# filtroFinal-TC.net
KiCad netlist of a schematic drawn in Altium Designer
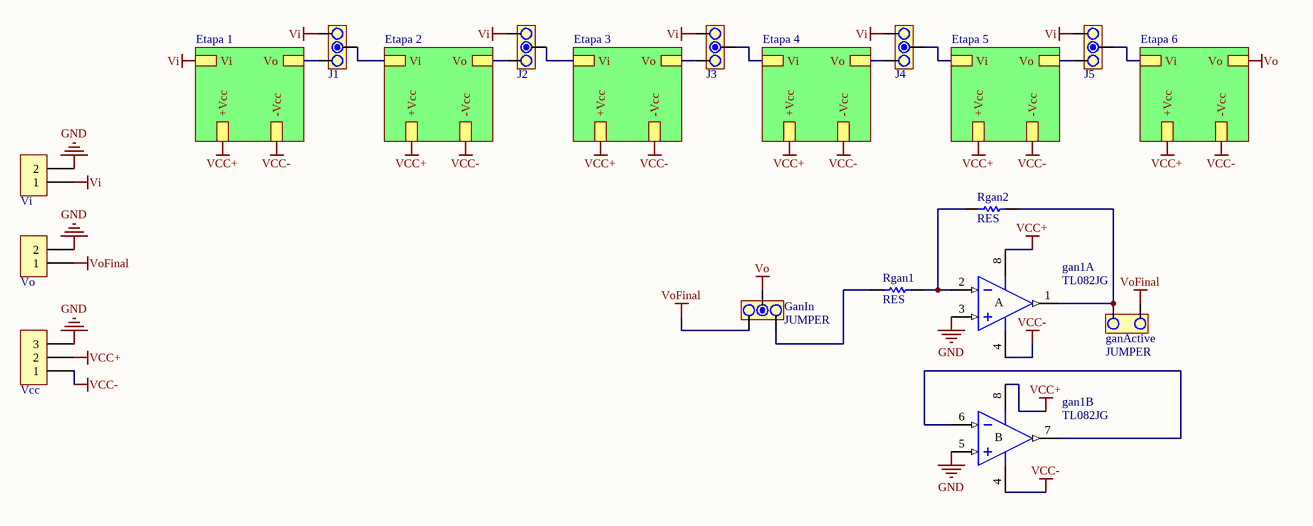
[diagram p0: filtroFinal-TC.SchDoc]

(export (version "E")
  (design (tool "Eeschema 10.0.6"))
  (components
    (comp (ref "gan1")
      (value "TL082JG")
      (footprint "JG008")
      (description "JFET-Input Operational Amplifier")
      (fields (field (name "PUBLISHER") "Altium Limited"))
      (libsource (lib "TI Operational Amplifier") (part "TL082JG"))
    )
    (comp (ref "ganActive")
      (value "JUMPER")
      (footprint "JUMPER2")
      (libsource (lib "LIBEBAL") (part "JUMPER"))
    )
    (comp (ref "GanIn") (value "JUMPER") (footprint "JUMPER3") (libsource (lib "") (part "JUMPER3_1")))
    (comp (ref "J1") (value "JUMPER") (footprint "JUMPER3") (libsource (lib "LIBEBAL") (part "JUMPER3")))
    (comp (ref "J2") (value "JUMPER") (footprint "JUMPER3") (libsource (lib "LIBEBAL") (part "JUMPER3")))
    (comp (ref "J3") (value "JUMPER") (footprint "JUMPER3") (libsource (lib "LIBEBAL") (part "JUMPER3")))
    (comp (ref "J4") (value "JUMPER") (footprint "JUMPER3") (libsource (lib "LIBEBAL") (part "JUMPER3")))
    (comp (ref "J5") (value "JUMPER") (footprint "JUMPER3") (libsource (lib "LIBEBAL") (part "JUMPER3")))
    (comp (ref "Rgan1") (value "RES") (footprint "RES300") (libsource (lib "LIBEBAL") (part "RES")))
    (comp (ref "Rgan2") (value "RES") (footprint "RES300") (libsource (lib "LIBEBAL") (part "RES")))
    (comp (ref "Vcc")
      (value "BORNERA 3")
      (footprint "BORNERA3")
      (libsource (lib "LIBEBAL") (part "BORNERA 3"))
    )
    (comp (ref "Vi")
      (value "BORNERA 2")
      (footprint "BORNERA2")
      (libsource (lib "LIBEBAL") (part "BORNERA 2"))
    )
    (comp (ref "Vo")
      (value "BORNERA 2")
      (footprint "BORNERA2")
      (libsource (lib "LIBEBAL") (part "BORNERA 2"))
    )
  )
  (nets
    (net (code "1") (name "/Vi") (class "Default")
      (node (ref "J2") (pin "2") (pinfunction "2_2") (pintype "passive"))
    )
    (net (code "2") (name "/Vi_1") (class "Default")
      (node (ref "J1") (pin "2") (pinfunction "2_2") (pintype "passive"))
    )
    (net (code "3") (name "/Vi_2") (class "Default")
      (node (ref "J3") (pin "2") (pinfunction "2_2") (pintype "passive"))
    )
    (net (code "4") (name "/Vi_3") (class "Default")
      (node (ref "J4") (pin "2") (pinfunction "2_2") (pintype "passive"))
    )
    (net (code "5") (name "/Vi_4") (class "Default")
      (node (ref "J5") (pin "2") (pinfunction "2_2") (pintype "passive"))
    )
    (net (code "6") (name "/Vo") (class "Default")
      (node (ref "J3") (pin "1") (pinfunction "1_1") (pintype "passive"))
    )
    (net (code "7") (name "/Vo_1") (class "Default")
      (node (ref "J1") (pin "1") (pinfunction "1_1") (pintype "passive"))
    )
    (net (code "8") (name "/Vo_2") (class "Default")
      (node (ref "J2") (pin "1") (pinfunction "1_1") (pintype "passive"))
    )
    (net (code "9") (name "/Vo_3") (class "Default")
      (node (ref "J4") (pin "1") (pinfunction "1_1") (pintype "passive"))
    )
    (net (code "10") (name "/Vo_4") (class "Default")
      (node (ref "J5") (pin "1") (pinfunction "1_1") (pintype "passive"))
    )
    (net (code "11") (name "GND") (class "Default")
      (node (ref "Vcc") (pin "3") (pinfunction "3_3") (pintype "passive"))
      (node (ref "Vi") (pin "2") (pinfunction "2_2") (pintype "passive"))
      (node (ref "Vo") (pin "2") (pinfunction "2_2") (pintype "passive"))
      (node (ref "gan1") (pin "3") (pinfunction "IN+_3") (pintype "input"))
      (node (ref "gan1") (pin "5") (pinfunction "IN+_5") (pintype "input"))
    )
    (net (code "12") (name "Net-(GanIn-Pad1)") (class "Default")
      (node (ref "GanIn") (pin "1") (pinfunction "1_1") (pintype "passive"))
      (node (ref "Rgan1") (pin "1") (pinfunction "1_1") (pintype "passive"))
    )
    (net (code "13") (name "Net-(gan1A-IN-)") (class "Default")
      (node (ref "Rgan1") (pin "2") (pinfunction "2_2") (pintype "passive"))
      (node (ref "Rgan2") (pin "1") (pinfunction "1_1") (pintype "passive"))
      (node (ref "gan1") (pin "2") (pinfunction "IN-_2") (pintype "input"))
    )
    (net (code "14") (name "Net-(gan1A-OUT)") (class "Default")
      (node (ref "Rgan2") (pin "2") (pinfunction "2_2") (pintype "passive"))
      (node (ref "gan1") (pin "1") (pinfunction "OUT_1") (pintype "output"))
      (node (ref "ganActive") (pin "1") (pinfunction "1_1") (pintype "passive"))
    )
    (net (code "15") (name "Net-(gan1B-IN-)") (class "Default")
      (node (ref "gan1") (pin "6") (pinfunction "IN-_6") (pintype "input"))
      (node (ref "gan1") (pin "7") (pinfunction "OUT_7") (pintype "output"))
    )
    (net (code "16") (name "VCC+") (class "Default")
      (node (ref "Vcc") (pin "2") (pinfunction "2_2") (pintype "passive"))
      (node (ref "gan1") (pin "8") (pinfunction "V+_8") (pintype "power_in"))
    )
    (net (code "17") (name "VCC-") (class "Default")
      (node (ref "Vcc") (pin "1") (pinfunction "1_1") (pintype "passive"))
      (node (ref "gan1") (pin "4") (pinfunction "V-_4") (pintype "power_in"))
    )
    (net (code "18") (name "Vi") (class "Default")
      (node (ref "J1") (pin "3") (pinfunction "3_3") (pintype "passive"))
      (node (ref "J2") (pin "3") (pinfunction "3_3") (pintype "passive"))
      (node (ref "J3") (pin "3") (pinfunction "3_3") (pintype "passive"))
      (node (ref "J4") (pin "3") (pinfunction "3_3") (pintype "passive"))
      (node (ref "J5") (pin "3") (pinfunction "3_3") (pintype "passive"))
      (node (ref "Vi") (pin "1") (pinfunction "1_1") (pintype "passive"))
    )
    (net (code "19") (name "Vo") (class "Default")
      (node (ref "GanIn") (pin "2") (pinfunction "2_2") (pintype "passive"))
    )
    (net (code "20") (name "VoFinal") (class "Default")
      (node (ref "GanIn") (pin "3") (pinfunction "3_3") (pintype "passive"))
      (node (ref "Vo") (pin "1") (pinfunction "1_1") (pintype "passive"))
      (node (ref "ganActive") (pin "2") (pinfunction "2_2") (pintype "passive"))
    )
  )
)
